# gas-sensor.net
KiCad netlist of a schematic drawn in Altium Designer
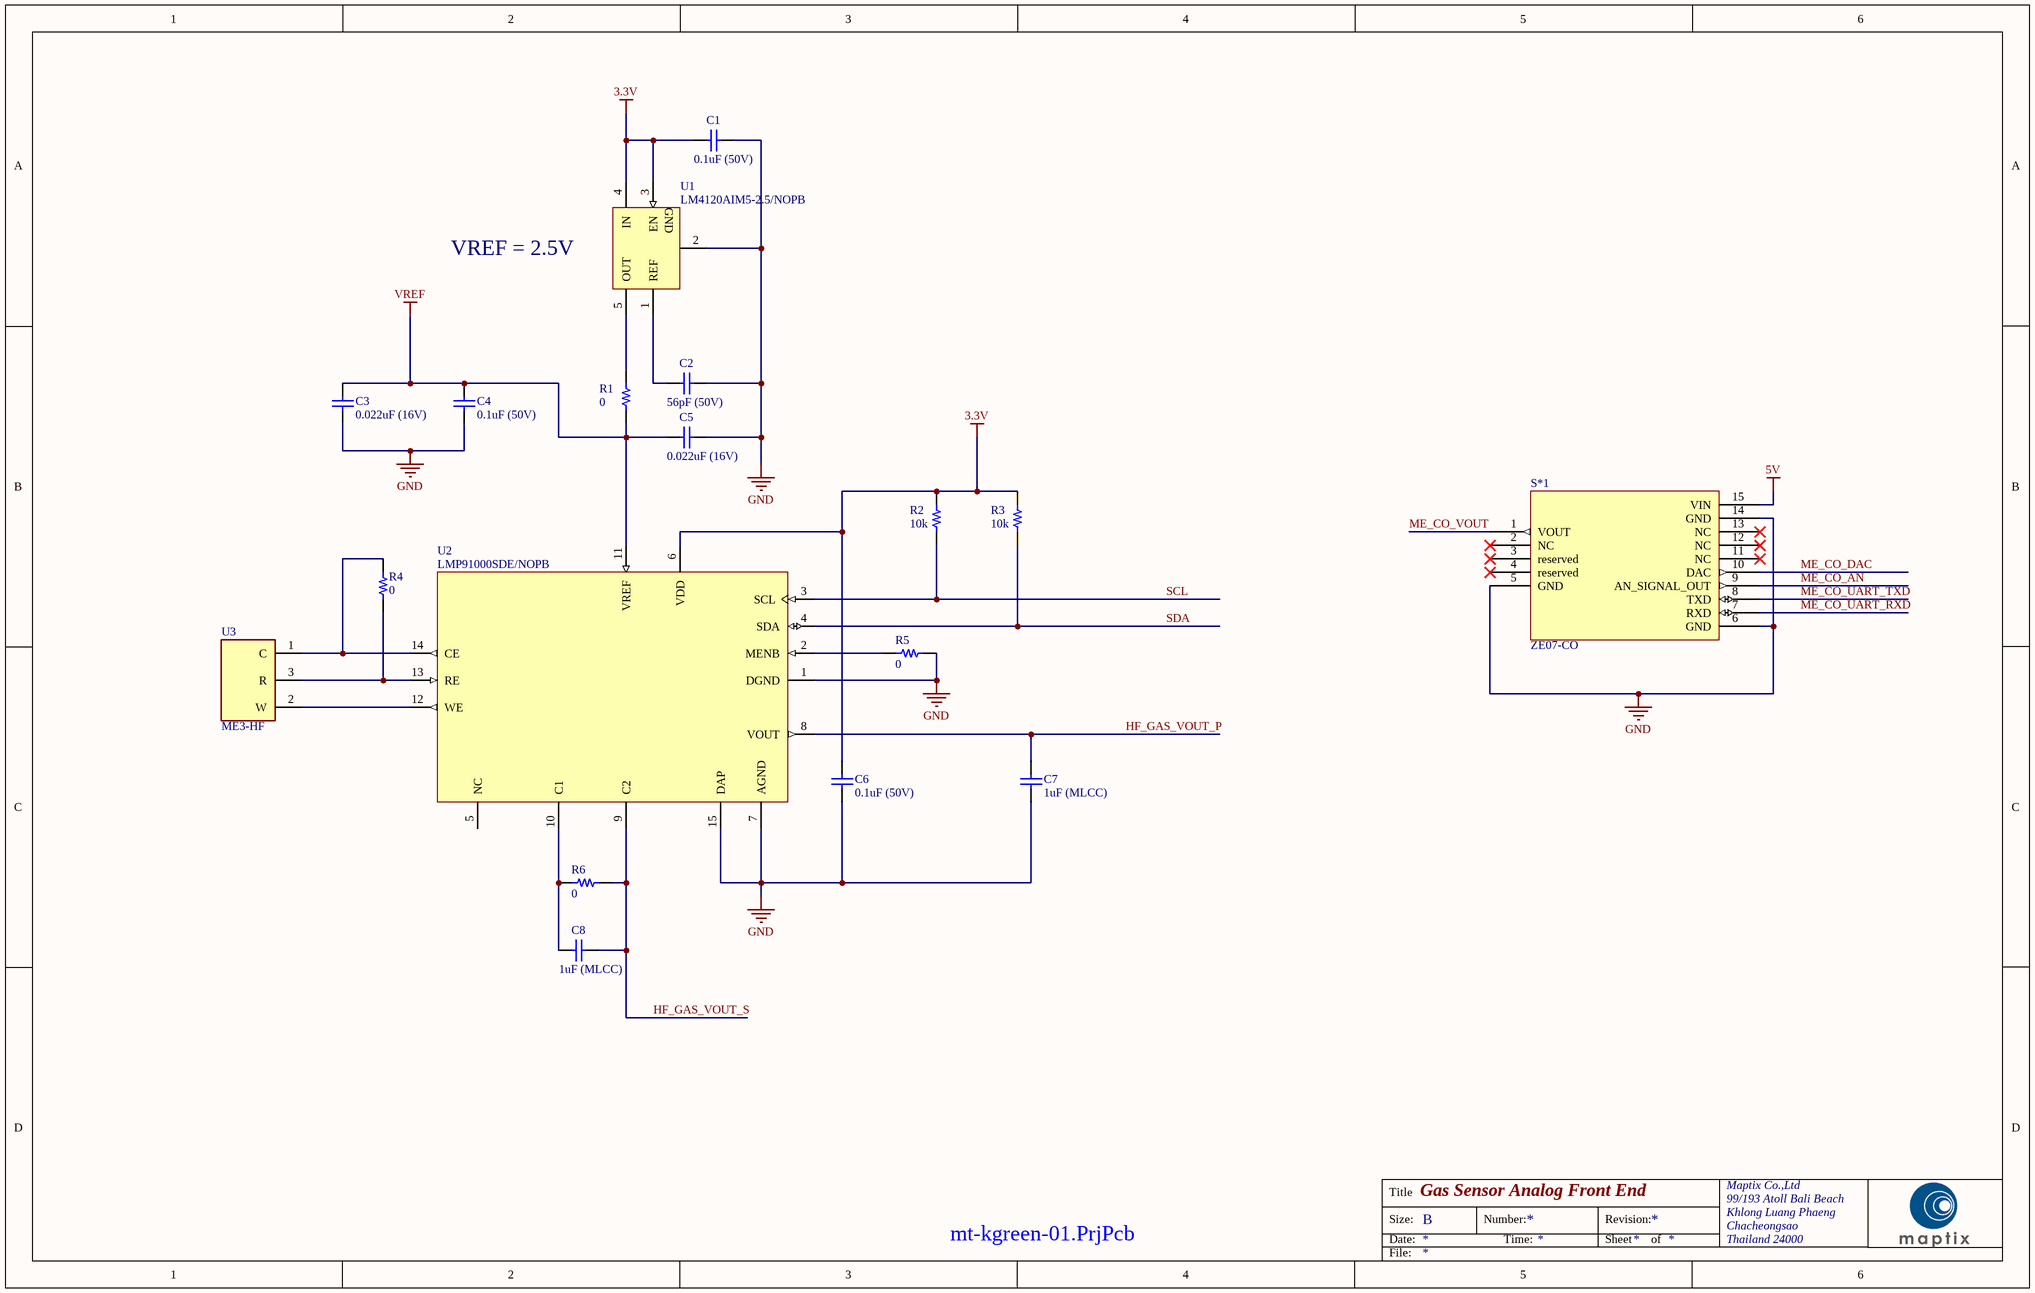
[diagram p0: gas-sensor.SchDoc]

(export (version "E")
  (design (tool "Eeschema 10.0.6"))
  (components
    (comp (ref "C1")
      (value "0.1uF (50V)")
      (footprint "CAPC1608X95X40NL15T15")
      (fields (field (name "PART NUMBER") "VJ0603Y332JXACW1BC") (field (name "MANUFACTURER") "Vitramon"))
      (libsource (lib "Altium Content Vault") (part "CAP"))
    )
    (comp (ref "C2")
      (value "56pF (50V)")
      (footprint "CAPC1608X95X40NL15T15")
      (fields (field (name "PART NUMBER") "VJ0603Y332JXACW1BC") (field (name "MANUFACTURER") "Vitramon"))
      (libsource (lib "Altium Content Vault") (part "CAP"))
    )
    (comp (ref "C3")
      (value "0.022uF (16V)")
      (footprint "CAPC1608X95X40NL15T15")
      (fields (field (name "PART NUMBER") "VJ0603Y332JXACW1BC") (field (name "MANUFACTURER") "Vitramon"))
      (libsource (lib "Altium Content Vault") (part "CAP"))
    )
    (comp (ref "C4")
      (value "0.1uF (50V)")
      (footprint "CAPC1608X95X40NL15T15")
      (fields (field (name "PART NUMBER") "VJ0603Y332JXACW1BC") (field (name "MANUFACTURER") "Vitramon"))
      (libsource (lib "Altium Content Vault") (part "CAP"))
    )
    (comp (ref "C5")
      (value "0.022uF (16V)")
      (footprint "CAPC1608X95X40NL15T15")
      (fields (field (name "PART NUMBER") "VJ0603Y332JXACW1BC") (field (name "MANUFACTURER") "Vitramon"))
      (libsource (lib "Altium Content Vault") (part "CAP"))
    )
    (comp (ref "C6")
      (value "0.1uF (50V)")
      (footprint "CAPC1608X95X40NL15T15")
      (fields (field (name "PART NUMBER") "VJ0603Y332JXACW1BC") (field (name "MANUFACTURER") "Vitramon"))
      (libsource (lib "Altium Content Vault") (part "CAP"))
    )
    (comp (ref "C7")
      (value "1uF (MLCC)")
      (footprint "CAPC1608X95X40NL15T15")
      (fields (field (name "PART NUMBER") "VJ0603Y332JXACW1BC") (field (name "MANUFACTURER") "Vitramon"))
      (libsource (lib "Altium Content Vault") (part "CAP"))
    )
    (comp (ref "C8")
      (value "1uF (MLCC)")
      (footprint "CAPC1608X95X40NL15T15")
      (fields (field (name "PART NUMBER") "VJ0603Y332JXACW1BC") (field (name "MANUFACTURER") "Vitramon"))
      (libsource (lib "Altium Content Vault") (part "CAP"))
    )
    (comp (ref "R1")
      (value "0")
      (footprint "RES 0603_1608")
      (description "Resistor")
      (fields (field (name "PART NUMBER") "CRCW060329K4FKEA") (field (name "MANUFACTURER") "Vishay Dale"))
      (libsource (lib "Celestial Altium Library - altium_library") (part "Resistor"))
    )
    (comp (ref "R2")
      (value "10k")
      (footprint "RES 0603_1608")
      (description "Resistor")
      (fields (field (name "PART NUMBER") "CRCW060329K4FKEA") (field (name "MANUFACTURER") "Vishay Dale"))
      (libsource (lib "Celestial Altium Library - altium_library") (part "Resistor"))
    )
    (comp (ref "R3")
      (value "10k")
      (footprint "RES 0603_1608")
      (description "Resistor")
      (fields (field (name "PART NUMBER") "CRCW060329K4FKEA") (field (name "MANUFACTURER") "Vishay Dale"))
      (libsource (lib "Celestial Altium Library - altium_library") (part "Resistor"))
    )
    (comp (ref "R4")
      (value "0")
      (footprint "RES 0603_1608")
      (description "Resistor")
      (fields (field (name "PART NUMBER") "CRCW060329K4FKEA") (field (name "MANUFACTURER") "Vishay Dale"))
      (libsource (lib "Celestial Altium Library - altium_library") (part "Resistor"))
    )
    (comp (ref "R5")
      (value "0")
      (footprint "RES 0603_1608")
      (description "Resistor")
      (fields (field (name "PART NUMBER") "CRCW060329K4FKEA") (field (name "MANUFACTURER") "Vishay Dale"))
      (libsource (lib "Celestial Altium Library - altium_library") (part "Resistor"))
    )
    (comp (ref "R6")
      (value "0")
      (footprint "RES 0603_1608")
      (description "Resistor")
      (fields (field (name "PART NUMBER") "CRCW060329K4FKEA") (field (name "MANUFACTURER") "Vishay Dale"))
      (libsource (lib "Celestial Altium Library - altium_library") (part "Resistor"))
    )
    (comp (ref "S*1") (value "ZE07-CO") (footprint "ZE07-CO") (libsource (lib "pae") (part "ZE07-CO")))
    (comp (ref "U1")
      (value "LM4120AIM5-2.5/NOPB")
      (footprint "MF05A_M")
      (description "Precision Micropower Low Dropout Voltage Reference, 5-pin SOT-23, Pb-Free")
      (fields (field (name "MANUFACTURER") "National Semiconductor"))
      (libsource (lib "Altium Content Vault") (part "PM-REF-LM4120-SOT5"))
    )
    (comp (ref "U2")
      (value "LMP91000SDE/NOPB")
      (footprint "NHL0014B_V_Pae")
      (description "Configurable AFE Potentiostat for Low-Power Chemical Sensing Applications, 14-pin LLP, 250 Reel")
      (fields (field (name "MANUFACTURER") "Texas Instruments"))
      (libsource (lib "Components - 24.02.20 - 00.40") (part "CMP-0064-00201-2"))
    )
    (comp (ref "U3")
      (value "ME3-HF")
      (footprint "SamacSys:ME3SO2")
      (description "Undefined or Miscellaneous")
      (fields (field (name "MANUFACTURER_PART_NUMBER") "ME3-SO2"))
      (libsource (lib "SamacSys") (part "ME3-SO2"))
    )
  )
  (nets
    (net (code "1") (name "/HF_GAS_VOUT_P") (class "Default")
      (node (ref "C7") (pin "1") (pinfunction "1_1") (pintype "passive"))
      (node (ref "U2") (pin "8") (pinfunction "VOUT_8") (pintype "output"))
    )
    (net (code "2") (name "/HF_GAS_VOUT_S") (class "Default")
      (node (ref "C8") (pin "1") (pinfunction "1_1") (pintype "passive"))
      (node (ref "R6") (pin "1") (pinfunction "1_1") (pintype "passive"))
      (node (ref "U2") (pin "9") (pinfunction "C2_9") (pintype "passive"))
    )
    (net (code "3") (name "/ME_CO_AN") (class "Default")
      (node (ref "S*1") (pin "9") (pinfunction "AN_SIGNAL_OUT_9") (pintype "output"))
    )
    (net (code "4") (name "/ME_CO_DAC") (class "Default")
      (node (ref "S*1") (pin "10") (pinfunction "DAC_10") (pintype "output"))
    )
    (net (code "5") (name "/ME_CO_UART_RXD") (class "Default")
      (node (ref "S*1") (pin "7") (pinfunction "RXD_7") (pintype "bidirectional"))
    )
    (net (code "6") (name "/ME_CO_UART_TXD") (class "Default")
      (node (ref "S*1") (pin "8") (pinfunction "TXD_8") (pintype "bidirectional"))
    )
    (net (code "7") (name "/ME_CO_VOUT") (class "Default")
      (node (ref "S*1") (pin "1") (pinfunction "VOUT_1") (pintype "output"))
    )
    (net (code "8") (name "/SCL") (class "Default")
      (node (ref "R2") (pin "1") (pinfunction "1_1") (pintype "passive"))
      (node (ref "U2") (pin "3") (pinfunction "SCL_3") (pintype "input"))
    )
    (net (code "9") (name "/SDA") (class "Default")
      (node (ref "R3") (pin "1") (pinfunction "1_1") (pintype "passive"))
      (node (ref "U2") (pin "4") (pinfunction "SDA_4") (pintype "bidirectional"))
    )
    (net (code "10") (name "3.3V") (class "Default")
      (node (ref "C1") (pin "2") (pinfunction "2_2") (pintype "passive"))
      (node (ref "C6") (pin "2") (pinfunction "2_2") (pintype "passive"))
      (node (ref "R2") (pin "2") (pinfunction "2_2") (pintype "passive"))
      (node (ref "R3") (pin "2") (pinfunction "2_2") (pintype "passive"))
      (node (ref "U1") (pin "3") (pinfunction "EN_3") (pintype "input"))
      (node (ref "U1") (pin "4") (pinfunction "IN_4") (pintype "power_in"))
      (node (ref "U2") (pin "6") (pinfunction "VDD_6") (pintype "power_in"))
    )
    (net (code "11") (name "5V") (class "Default")
      (node (ref "S*1") (pin "15") (pinfunction "VIN_15") (pintype "power_in"))
    )
    (net (code "12") (name "GND") (class "Default")
      (node (ref "C1") (pin "1") (pinfunction "1_1") (pintype "passive"))
      (node (ref "C2") (pin "1") (pinfunction "1_1") (pintype "passive"))
      (node (ref "C3") (pin "2") (pinfunction "2_2") (pintype "passive"))
      (node (ref "C4") (pin "1") (pinfunction "1_1") (pintype "passive"))
      (node (ref "C5") (pin "1") (pinfunction "1_1") (pintype "passive"))
      (node (ref "C6") (pin "1") (pinfunction "1_1") (pintype "passive"))
      (node (ref "C7") (pin "2") (pinfunction "2_2") (pintype "passive"))
      (node (ref "R5") (pin "1") (pinfunction "1_1") (pintype "passive"))
      (node (ref "S*1") (pin "14") (pinfunction "GND_14") (pintype "power_in"))
      (node (ref "S*1") (pin "5") (pinfunction "GND_5") (pintype "power_in"))
      (node (ref "S*1") (pin "6") (pinfunction "GND_6") (pintype "power_in"))
      (node (ref "U1") (pin "2") (pinfunction "GND_2") (pintype "power_in"))
      (node (ref "U2") (pin "1") (pinfunction "DGND_1") (pintype "power_in"))
      (node (ref "U2") (pin "15") (pinfunction "DAP_15") (pintype "power_in"))
      (node (ref "U2") (pin "7") (pinfunction "AGND_7") (pintype "power_in"))
    )
    (net (code "13") (name "Net-(U1-OUT)") (class "Default")
      (node (ref "R1") (pin "2") (pinfunction "2_2") (pintype "passive"))
      (node (ref "U1") (pin "5") (pinfunction "OUT_5") (pintype "power_in"))
    )
    (net (code "14") (name "Net-(U1-REF)") (class "Default")
      (node (ref "C2") (pin "2") (pinfunction "2_2") (pintype "passive"))
      (node (ref "U1") (pin "1") (pinfunction "REF_1") (pintype "passive"))
    )
    (net (code "15") (name "Net-(U2-C1)") (class "Default")
      (node (ref "C8") (pin "2") (pinfunction "2_2") (pintype "passive"))
      (node (ref "R6") (pin "2") (pinfunction "2_2") (pintype "passive"))
      (node (ref "U2") (pin "10") (pinfunction "C1_10") (pintype "passive"))
    )
    (net (code "16") (name "Net-(U2-CE)") (class "Default")
      (node (ref "R4") (pin "1") (pinfunction "1_1") (pintype "passive"))
      (node (ref "U2") (pin "14") (pinfunction "CE_14") (pintype "output"))
      (node (ref "U3") (pin "1") (pinfunction "C_1") (pintype "passive"))
    )
    (net (code "17") (name "Net-(U2-MENB)") (class "Default")
      (node (ref "R5") (pin "2") (pinfunction "2_2") (pintype "passive"))
      (node (ref "U2") (pin "2") (pinfunction "MENB_2") (pintype "input"))
    )
    (net (code "18") (name "Net-(U2-RE)") (class "Default")
      (node (ref "R4") (pin "2") (pinfunction "2_2") (pintype "passive"))
      (node (ref "U2") (pin "13") (pinfunction "RE_13") (pintype "input"))
      (node (ref "U3") (pin "3") (pinfunction "R_3") (pintype "passive"))
    )
    (net (code "19") (name "Net-(U2-WE)") (class "Default")
      (node (ref "U2") (pin "12") (pinfunction "WE_12") (pintype "output"))
      (node (ref "U3") (pin "2") (pinfunction "W_2") (pintype "passive"))
    )
    (net (code "20") (name "VREF") (class "Default")
      (node (ref "C3") (pin "1") (pinfunction "1_1") (pintype "passive"))
      (node (ref "C4") (pin "2") (pinfunction "2_2") (pintype "passive"))
      (node (ref "C5") (pin "2") (pinfunction "2_2") (pintype "passive"))
      (node (ref "R1") (pin "1") (pinfunction "1_1") (pintype "passive"))
      (node (ref "U2") (pin "11") (pinfunction "VREF_11") (pintype "input"))
    )
    (net (code "21") (name "unconnected-(S*1-NC-Pad2)") (class "Default")
      (node (ref "S*1") (pin "2") (pinfunction "NC_2") (pintype "passive+no_connect"))
    )
    (net (code "22") (name "unconnected-(S*1-NC-Pad11)") (class "Default")
      (node (ref "S*1") (pin "11") (pinfunction "NC_11") (pintype "passive+no_connect"))
    )
    (net (code "23") (name "unconnected-(S*1-NC-Pad12)") (class "Default")
      (node (ref "S*1") (pin "12") (pinfunction "NC_12") (pintype "passive+no_connect"))
    )
    (net (code "24") (name "unconnected-(S*1-NC-Pad13)") (class "Default")
      (node (ref "S*1") (pin "13") (pinfunction "NC_13") (pintype "passive+no_connect"))
    )
    (net (code "25") (name "unconnected-(S*1-reserved-Pad3)") (class "Default")
      (node (ref "S*1") (pin "3") (pinfunction "reserved_3") (pintype "passive+no_connect"))
    )
    (net (code "26") (name "unconnected-(S*1-reserved-Pad4)") (class "Default")
      (node (ref "S*1") (pin "4") (pinfunction "reserved_4") (pintype "passive+no_connect"))
    )
    (net (code "27") (name "unconnected-(U2-NC-Pad5)") (class "Default")
      (node (ref "U2") (pin "5") (pinfunction "NC_5") (pintype "passive"))
    )
  )
)
